# integratedBertha.net
KiCad netlist of a schematic drawn in EAGLE
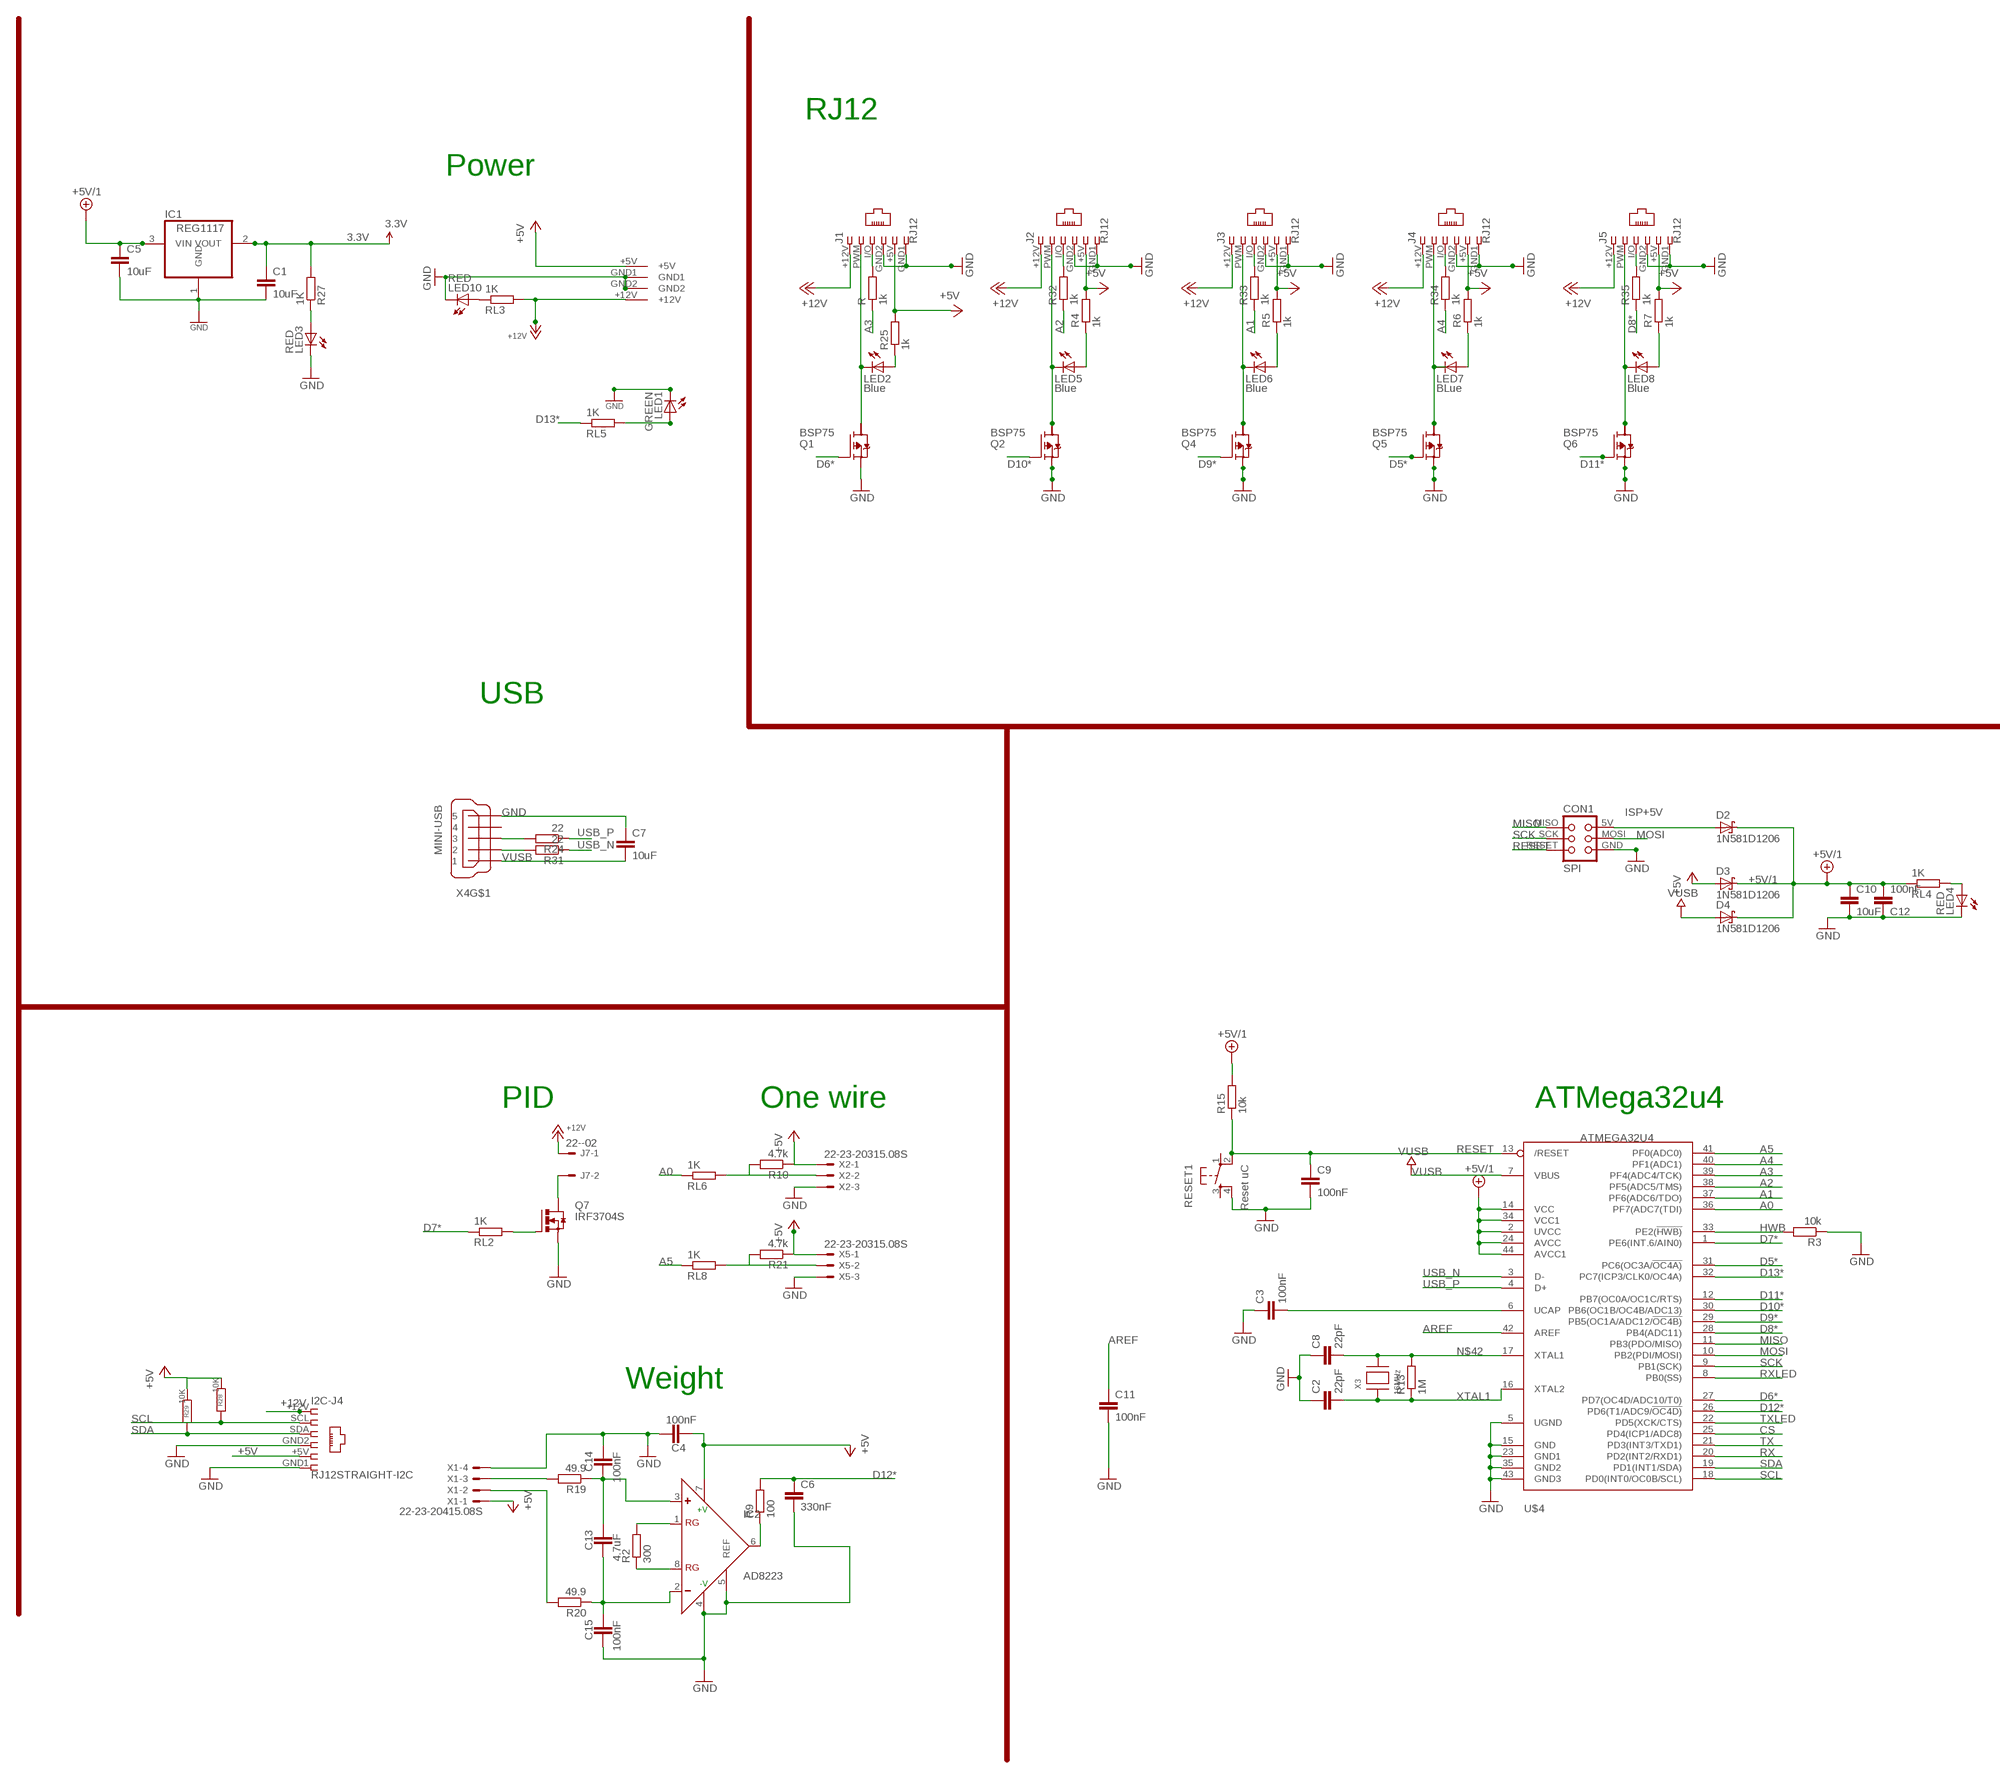
[diagram p0: schematic, sheet 1, part 1 of 2]
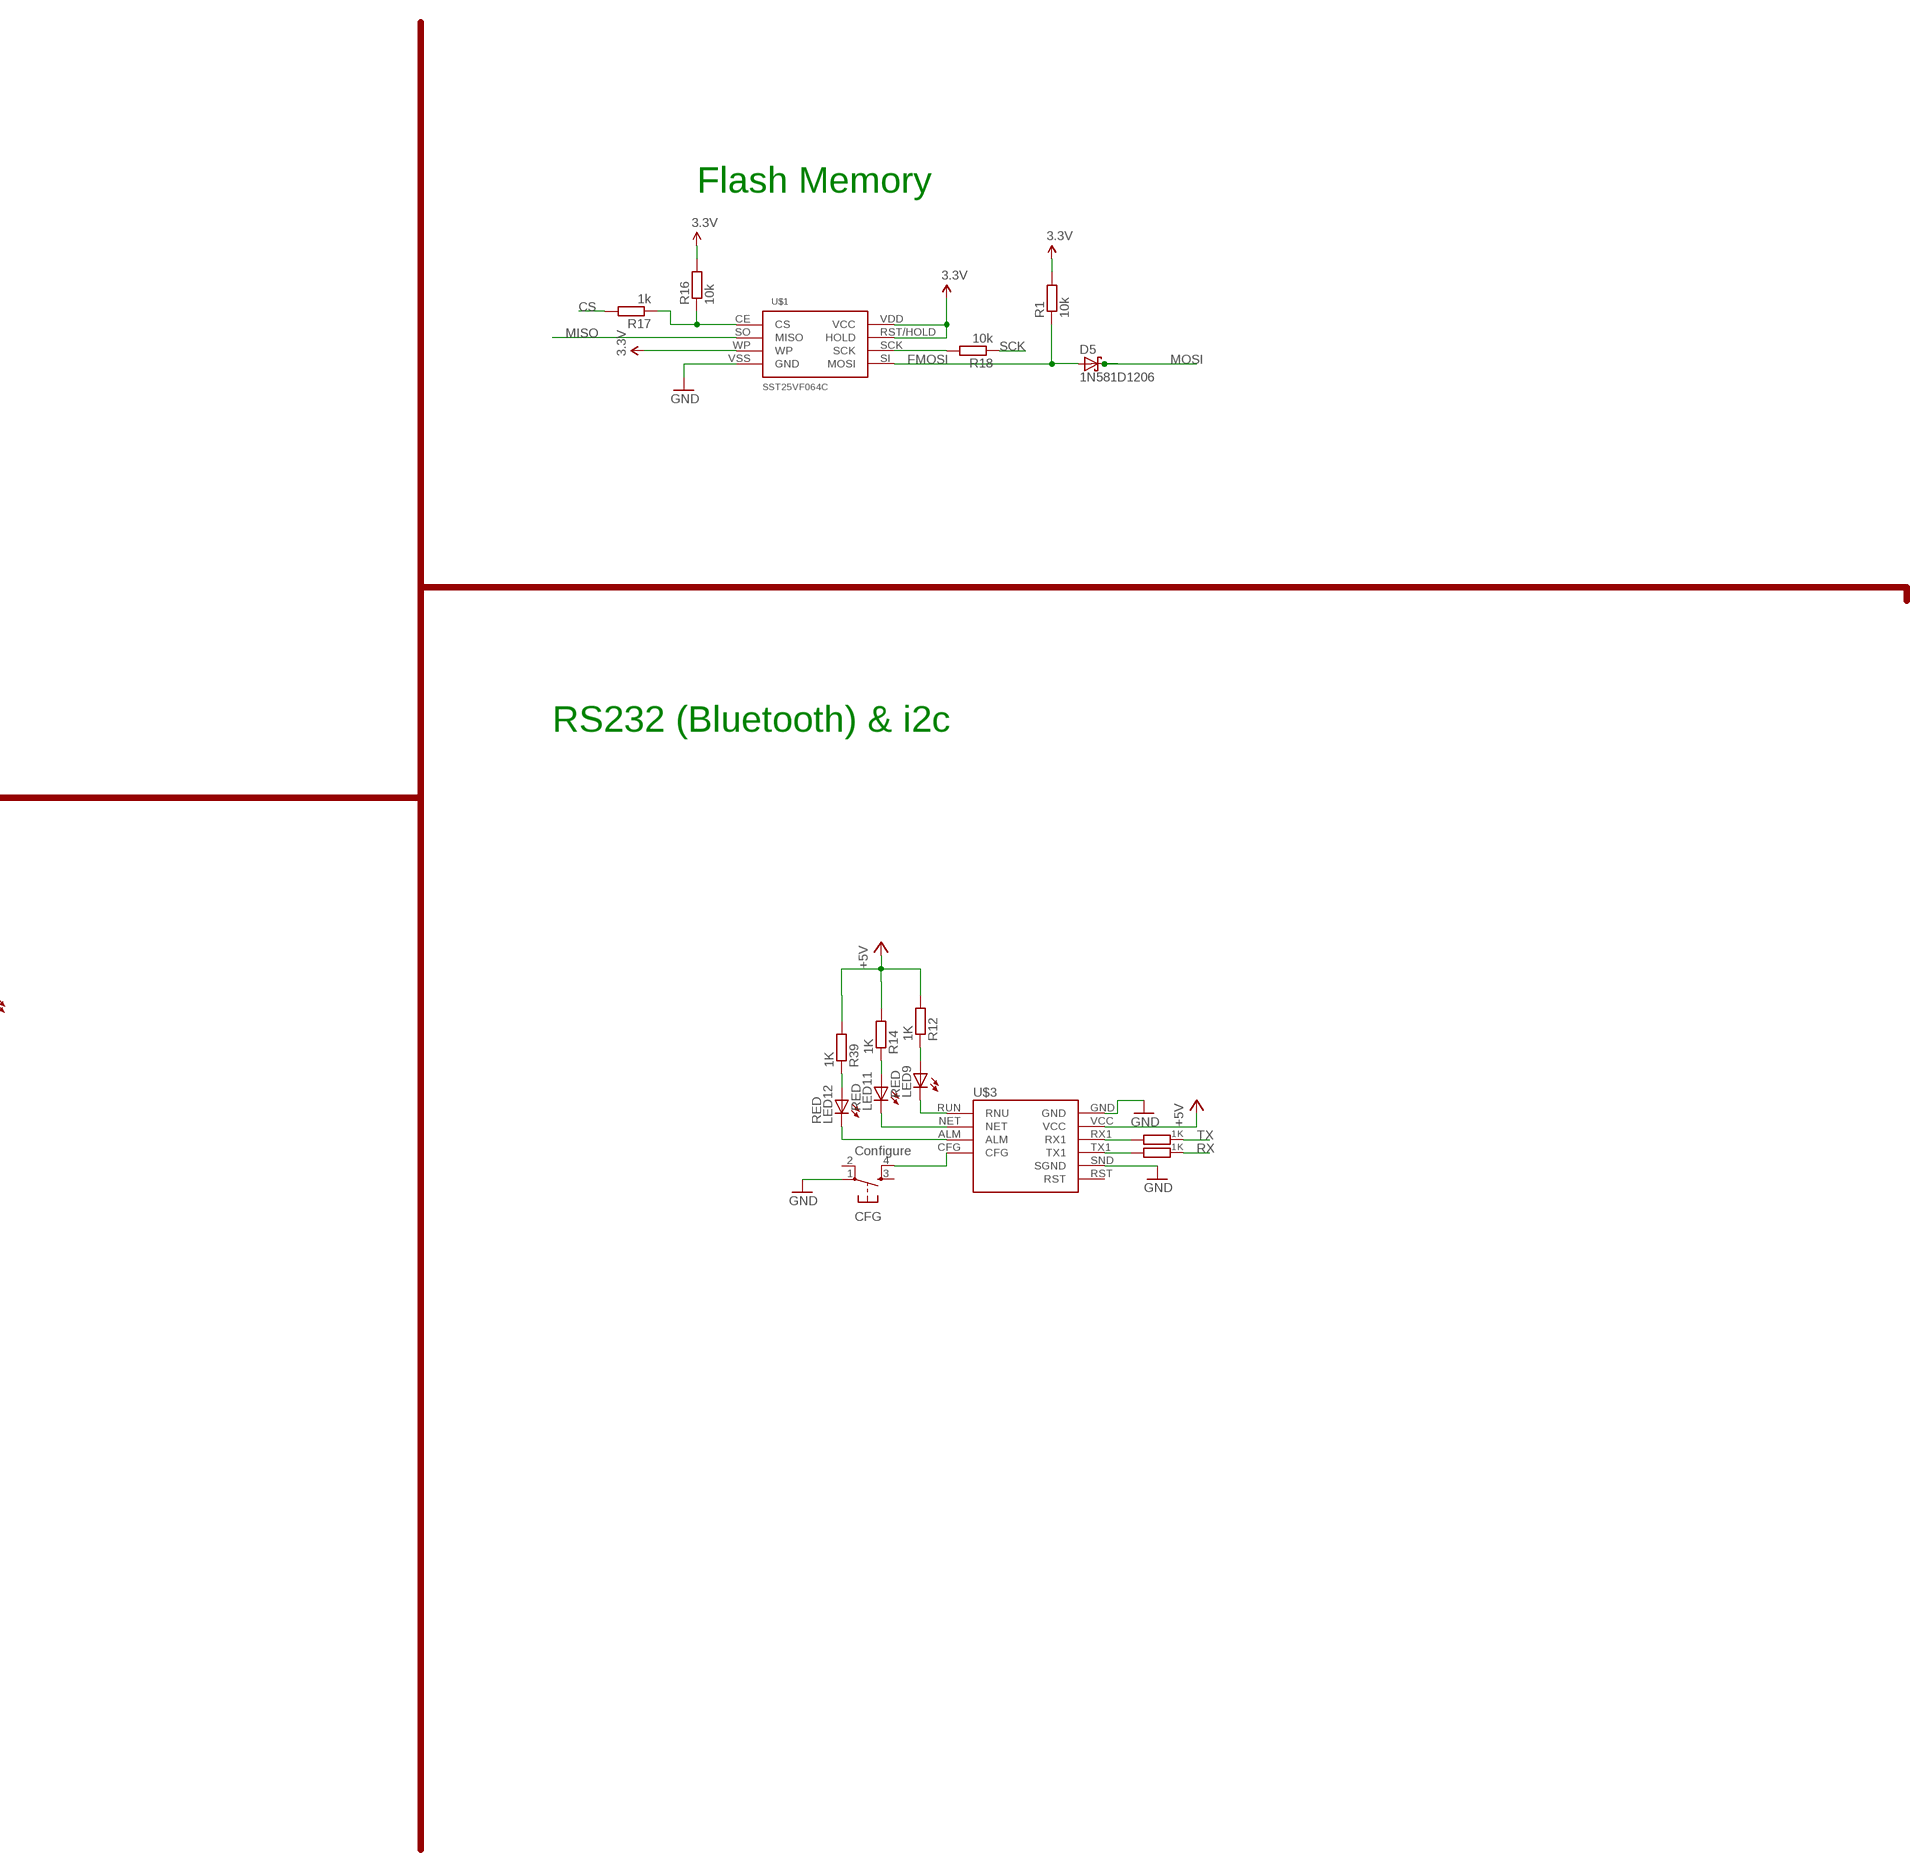
[diagram p1: schematic, sheet 1, part 2 of 2]

(export (version "E")
  (design (tool "Eeschema 10.0.6"))
  (components
    (comp (ref "C1")
      (value "10uF")
      (footprint "eagle-import:C1206")
      (libsource (lib "eagle-import") (part "C-EUC1206"))
    )
    (comp (ref "C2")
      (value "22pF")
      (footprint "eagle-import:C1206")
      (libsource (lib "eagle-import") (part "C-EUC1206"))
    )
    (comp (ref "C3")
      (value "100nF")
      (footprint "eagle-import:C1206")
      (libsource (lib "eagle-import") (part "C-EUC1206"))
    )
    (comp (ref "C4")
      (value "100nF")
      (footprint "eagle-import:C1206")
      (libsource (lib "eagle-import") (part "C-EUC1206"))
    )
    (comp (ref "C5")
      (value "10uF")
      (footprint "eagle-import:C1206")
      (libsource (lib "eagle-import") (part "C-EUC1206"))
    )
    (comp (ref "C6")
      (value "330nF")
      (footprint "eagle-import:C1206")
      (libsource (lib "eagle-import") (part "C-EUC1206"))
    )
    (comp (ref "C7")
      (value "10uF")
      (footprint "eagle-import:C1206")
      (libsource (lib "eagle-import") (part "C-EUC1206"))
    )
    (comp (ref "C8")
      (value "22pF")
      (footprint "eagle-import:C1206")
      (libsource (lib "eagle-import") (part "C-EUC1206"))
    )
    (comp (ref "C9")
      (value "100nF")
      (footprint "eagle-import:C1206")
      (libsource (lib "eagle-import") (part "C-EUC1206"))
    )
    (comp (ref "C10")
      (value "10uF")
      (footprint "eagle-import:C1206")
      (libsource (lib "eagle-import") (part "C-EUC1206"))
    )
    (comp (ref "C11")
      (value "100nF")
      (footprint "eagle-import:C1206")
      (libsource (lib "eagle-import") (part "C-EUC1206"))
    )
    (comp (ref "C12")
      (value "100nF")
      (footprint "eagle-import:C1206")
      (libsource (lib "eagle-import") (part "C-EUC1206"))
    )
    (comp (ref "C13")
      (value "4.7uF")
      (footprint "eagle-import:C1206")
      (libsource (lib "eagle-import") (part "C-EUC1206"))
    )
    (comp (ref "C14")
      (value "100nF")
      (footprint "eagle-import:C1206")
      (libsource (lib "eagle-import") (part "C-EUC1206"))
    )
    (comp (ref "C15")
      (value "100nF")
      (footprint "eagle-import:C1206")
      (libsource (lib "eagle-import") (part "C-EUC1206"))
    )
    (comp (ref "CFG")
      (value "Configure")
      (footprint "eagle-import:TACTILE_SWITCH_SMD")
      (libsource (lib "eagle-import") (part "TAC_SWITCHSMD"))
    )
    (comp (ref "CON1")
      (value "SPI")
      (footprint "eagle-import:TC2030-MCP-NL")
      (libsource (lib "eagle-import") (part "TINYISPT"))
    )
    (comp (ref "D2")
      (value "1N581D1206")
      (footprint "eagle-import:LED-1206")
      (libsource (lib "eagle-import") (part "1N581D1206"))
    )
    (comp (ref "D3")
      (value "1N581D1206")
      (footprint "eagle-import:LED-1206")
      (libsource (lib "eagle-import") (part "1N581D1206"))
    )
    (comp (ref "D4")
      (value "1N581D1206")
      (footprint "eagle-import:LED-1206")
      (libsource (lib "eagle-import") (part "1N581D1206"))
    )
    (comp (ref "D5")
      (value "1N581D1206")
      (footprint "eagle-import:LED-1206")
      (libsource (lib "eagle-import") (part "1N581D1206"))
    )
    (comp (ref "I2C-J4")
      (value "RJ12STRAIGHT-I2C")
      (footprint "eagle-import:RJ12-STRAIGHT-I2C")
      (libsource (lib "eagle-import") (part "RJ12STRAIGHT-I2C"))
    )
    (comp (ref "IC1")
      (value "REG1117")
      (footprint "eagle-import:SOT223")
      (libsource (lib "eagle-import") (part "REG1117"))
    )
    (comp (ref "IC2")
      (value "AD8223")
      (footprint "eagle-import:SO8")
      (fields (field (name "MPN") "AD620AR"))
      (libsource (lib "eagle-import") (part "AD620R"))
    )
    (comp (ref "J1")
      (value "RJ12")
      (footprint "eagle-import:RJ12-STRAIGHT")
      (libsource (lib "eagle-import") (part "RJ12STRAIGHT"))
    )
    (comp (ref "J2")
      (value "RJ12")
      (footprint "eagle-import:RJ12-STRAIGHT")
      (libsource (lib "eagle-import") (part "RJ12STRAIGHT"))
    )
    (comp (ref "J3")
      (value "RJ12")
      (footprint "eagle-import:RJ12-STRAIGHT")
      (libsource (lib "eagle-import") (part "RJ12STRAIGHT"))
    )
    (comp (ref "J4")
      (value "RJ12")
      (footprint "eagle-import:RJ12-STRAIGHT")
      (libsource (lib "eagle-import") (part "RJ12STRAIGHT"))
    )
    (comp (ref "J5")
      (value "RJ12")
      (footprint "eagle-import:RJ12-STRAIGHT")
      (libsource (lib "eagle-import") (part "RJ12STRAIGHT"))
    )
    (comp (ref "J7")
      (value "22--02")
      (footprint "eagle-import:2-PIN-5.08S")
      (libsource (lib "eagle-import") (part "22-?-02"))
    )
    (comp (ref "LED1")
      (value "GREEN")
      (footprint "eagle-import:CHIPLED_1206")
      (libsource (lib "eagle-import") (part "LEDCHIPLED_1206"))
    )
    (comp (ref "LED2")
      (value "Blue")
      (footprint "eagle-import:CHIPLED_1206")
      (libsource (lib "eagle-import") (part "LEDCHIPLED_1206"))
    )
    (comp (ref "LED3")
      (value "RED")
      (footprint "eagle-import:CHIPLED_1206")
      (libsource (lib "eagle-import") (part "LEDCHIPLED_1206"))
    )
    (comp (ref "LED4")
      (value "RED")
      (footprint "eagle-import:CHIPLED_1206")
      (libsource (lib "eagle-import") (part "LEDCHIPLED_1206"))
    )
    (comp (ref "LED5")
      (value "Blue")
      (footprint "eagle-import:CHIPLED_1206")
      (libsource (lib "eagle-import") (part "LEDCHIPLED_1206"))
    )
    (comp (ref "LED6")
      (value "Blue")
      (footprint "eagle-import:CHIPLED_1206")
      (libsource (lib "eagle-import") (part "LEDCHIPLED_1206"))
    )
    (comp (ref "LED7")
      (value "BLue")
      (footprint "eagle-import:CHIPLED_1206")
      (libsource (lib "eagle-import") (part "LEDCHIPLED_1206"))
    )
    (comp (ref "LED8")
      (value "Blue")
      (footprint "eagle-import:CHIPLED_1206")
      (libsource (lib "eagle-import") (part "LEDCHIPLED_1206"))
    )
    (comp (ref "LED9")
      (value "RED")
      (footprint "eagle-import:CHIPLED_1206")
      (libsource (lib "eagle-import") (part "LEDCHIPLED_1206"))
    )
    (comp (ref "LED10")
      (value "RED")
      (footprint "eagle-import:CHIPLED_1206")
      (libsource (lib "eagle-import") (part "LEDCHIPLED_1206"))
    )
    (comp (ref "LED11")
      (value "RED")
      (footprint "eagle-import:CHIPLED_1206")
      (libsource (lib "eagle-import") (part "LEDCHIPLED_1206"))
    )
    (comp (ref "LED12")
      (value "RED")
      (footprint "eagle-import:CHIPLED_1206")
      (libsource (lib "eagle-import") (part "LEDCHIPLED_1206"))
    )
    (comp (ref "Q1")
      (value "BSP75")
      (footprint "eagle-import:PG-SOT-223")
      (libsource (lib "eagle-import") (part "BSP613P"))
    )
    (comp (ref "Q2")
      (value "BSP75")
      (footprint "eagle-import:PG-SOT-223")
      (libsource (lib "eagle-import") (part "BSP613P"))
    )
    (comp (ref "Q4")
      (value "BSP75")
      (footprint "eagle-import:PG-SOT-223")
      (libsource (lib "eagle-import") (part "BSP613P"))
    )
    (comp (ref "Q5")
      (value "BSP75")
      (footprint "eagle-import:PG-SOT-223")
      (libsource (lib "eagle-import") (part "BSP613P"))
    )
    (comp (ref "Q6")
      (value "BSP75")
      (footprint "eagle-import:PG-SOT-223")
      (libsource (lib "eagle-import") (part "BSP613P"))
    )
    (comp (ref "Q7")
      (value "IRF3704S")
      (footprint "eagle-import:D2PACK")
      (libsource (lib "eagle-import") (part "IRF3704S"))
    )
    (comp (ref "R")
      (value "1k")
      (footprint "eagle-import:R0805")
      (libsource (lib "eagle-import") (part "R-EU_R0805"))
    )
    (comp (ref "R1")
      (value "10k")
      (footprint "eagle-import:R0805")
      (libsource (lib "eagle-import") (part "R-EU_R0805"))
    )
    (comp (ref "R2")
      (value "300")
      (footprint "eagle-import:R1206")
      (libsource (lib "eagle-import") (part "resistor_R-EU_R1206"))
    )
    (comp (ref "R3")
      (value "10k")
      (footprint "eagle-import:M0805")
      (libsource (lib "eagle-import") (part "resistor_R-EU_M0805"))
    )
    (comp (ref "R4")
      (value "1k")
      (footprint "eagle-import:R0805")
      (libsource (lib "eagle-import") (part "R-EU_R0805"))
    )
    (comp (ref "R5")
      (value "1k")
      (footprint "eagle-import:R0805")
      (libsource (lib "eagle-import") (part "R-EU_R0805"))
    )
    (comp (ref "R6")
      (value "1k")
      (footprint "eagle-import:R0805")
      (libsource (lib "eagle-import") (part "R-EU_R0805"))
    )
    (comp (ref "R7")
      (value "1k")
      (footprint "eagle-import:R0805")
      (libsource (lib "eagle-import") (part "R-EU_R0805"))
    )
    (comp (ref "R8")
      (value "1K")
      (footprint "eagle-import:R0805")
      (libsource (lib "eagle-import") (part "R-EU_R0805"))
    )
    (comp (ref "R9")
      (value "100")
      (footprint "eagle-import:R1206")
      (libsource (lib "eagle-import") (part "resistor_R-EU_R1206"))
    )
    (comp (ref "R10")
      (value "4.7k")
      (footprint "eagle-import:R1206")
      (libsource (lib "eagle-import") (part "resistor_R-EU_R1206"))
    )
    (comp (ref "R11")
      (value "1K")
      (footprint "eagle-import:R0805")
      (libsource (lib "eagle-import") (part "R-EU_R0805"))
    )
    (comp (ref "R12")
      (value "1K")
      (footprint "eagle-import:R0805")
      (libsource (lib "eagle-import") (part "R-EU_R0805"))
    )
    (comp (ref "R13")
      (value "1M")
      (footprint "eagle-import:R1206")
      (libsource (lib "eagle-import") (part "R-EU_R1206"))
    )
    (comp (ref "R14")
      (value "1K")
      (footprint "eagle-import:R0805")
      (libsource (lib "eagle-import") (part "R-EU_R0805"))
    )
    (comp (ref "R15")
      (value "10k")
      (footprint "eagle-import:M0805")
      (libsource (lib "eagle-import") (part "resistor_R-EU_M0805"))
    )
    (comp (ref "R16")
      (value "10k")
      (footprint "eagle-import:R0805")
      (libsource (lib "eagle-import") (part "R-EU_R0805"))
    )
    (comp (ref "R17")
      (value "1k")
      (footprint "eagle-import:R0805")
      (libsource (lib "eagle-import") (part "R-EU_R0805"))
    )
    (comp (ref "R18")
      (value "10k")
      (footprint "eagle-import:R0805")
      (libsource (lib "eagle-import") (part "R-EU_R0805"))
    )
    (comp (ref "R19")
      (value "49.9")
      (footprint "eagle-import:R1206")
      (libsource (lib "eagle-import") (part "resistor_R-EU_R1206"))
    )
    (comp (ref "R20")
      (value "49.9")
      (footprint "eagle-import:R1206")
      (libsource (lib "eagle-import") (part "resistor_R-EU_R1206"))
    )
    (comp (ref "R21")
      (value "4.7k")
      (footprint "eagle-import:R1206")
      (libsource (lib "eagle-import") (part "resistor_R-EU_R1206"))
    )
    (comp (ref "R24")
      (value "22")
      (footprint "eagle-import:M1206")
      (libsource (lib "eagle-import") (part "resistor_R-EU_M1206"))
    )
    (comp (ref "R25")
      (value "1k")
      (footprint "eagle-import:R0805")
      (libsource (lib "eagle-import") (part "R-EU_R0805"))
    )
    (comp (ref "R27")
      (value "1K")
      (footprint "eagle-import:R0805")
      (libsource (lib "eagle-import") (part "R-EU_R0805"))
    )
    (comp (ref "R28")
      (value "10K")
      (footprint "eagle-import:M0805")
      (libsource (lib "eagle-import") (part "resistor_R-EU_M0805"))
    )
    (comp (ref "R29")
      (value "10K")
      (footprint "eagle-import:M0805")
      (libsource (lib "eagle-import") (part "resistor_R-EU_M0805"))
    )
    (comp (ref "R31")
      (value "22")
      (footprint "eagle-import:M1206")
      (libsource (lib "eagle-import") (part "resistor_R-EU_M1206"))
    )
    (comp (ref "R32")
      (value "1k")
      (footprint "eagle-import:R0805")
      (libsource (lib "eagle-import") (part "R-EU_R0805"))
    )
    (comp (ref "R33")
      (value "1k")
      (footprint "eagle-import:R0805")
      (libsource (lib "eagle-import") (part "R-EU_R0805"))
    )
    (comp (ref "R34")
      (value "1k")
      (footprint "eagle-import:R0805")
      (libsource (lib "eagle-import") (part "R-EU_R0805"))
    )
    (comp (ref "R35")
      (value "1k")
      (footprint "eagle-import:R0805")
      (libsource (lib "eagle-import") (part "R-EU_R0805"))
    )
    (comp (ref "R39")
      (value "1K")
      (footprint "eagle-import:R0805")
      (libsource (lib "eagle-import") (part "R-EU_R0805"))
    )
    (comp (ref "RESET1")
      (value "Reset uC")
      (footprint "eagle-import:TACTILE_SWITCH_SMD")
      (libsource (lib "eagle-import") (part "TAC_SWITCHSMD"))
    )
    (comp (ref "RL2")
      (value "1K")
      (footprint "eagle-import:R0805")
      (libsource (lib "eagle-import") (part "R-EU_R0805"))
    )
    (comp (ref "RL3")
      (value "1K")
      (footprint "eagle-import:R0805")
      (libsource (lib "eagle-import") (part "R-EU_R0805"))
    )
    (comp (ref "RL4")
      (value "1K")
      (footprint "eagle-import:R0805")
      (libsource (lib "eagle-import") (part "resistor_R-EU_R0805"))
    )
    (comp (ref "RL5")
      (value "1K")
      (footprint "eagle-import:R0805")
      (libsource (lib "eagle-import") (part "R-EU_R0805"))
    )
    (comp (ref "RL6")
      (value "1K")
      (footprint "eagle-import:R0805")
      (libsource (lib "eagle-import") (part "R-EU_R0805"))
    )
    (comp (ref "RL8")
      (value "1K")
      (footprint "eagle-import:R0805")
      (libsource (lib "eagle-import") (part "R-EU_R0805"))
    )
    (comp (ref "U$1")
      (value "SST25VF064C")
      (footprint "eagle-import:SOIC_8-LEAD")
      (libsource (lib "eagle-import") (part "SST25VF064C"))
    )
    (comp (ref "U$3")
      (value "SZ05-ZIGBEETHROUGHHOLE")
      (footprint "eagle-import:SZ05-ZIGBEE4")
      (libsource (lib "eagle-import") (part "SZ05-ZIGBEETHROUGHHOLE"))
    )
    (comp (ref "U$4")
      (value "ATMEGA32U4")
      (footprint "eagle-import:TQFP44")
      (libsource (lib "eagle-import") (part "ATMEGA32U4-AU"))
    )
    (comp (ref "U$6")
      (value "KPJX-4S-S")
      (footprint "eagle-import:KPJX-4S-S")
      (libsource (lib "eagle-import") (part "KPJX-4S-S"))
    )
    (comp (ref "X1")
      (value "22-23-20415.08S")
      (footprint "eagle-import:4-PIN-5.08S")
      (libsource (lib "eagle-import") (part "22-23-20415.08S"))
    )
    (comp (ref "X2")
      (value "22-23-20315.08S")
      (footprint "eagle-import:3-PIN-5.08S")
      (libsource (lib "eagle-import") (part "22-23-20315.08S"))
    )
    (comp (ref "X3")
      (value "16MHz")
      (footprint "eagle-import:NX6035")
      (libsource (lib "eagle-import") (part "XTALNX6035"))
    )
    (comp (ref "X4")
      (value "MINI-USB")
      (footprint "eagle-import:32005-201")
      (libsource (lib "eagle-import") (part "MINI-USB-SCHIELD-32005-201"))
    )
    (comp (ref "X5")
      (value "22-23-20315.08S")
      (footprint "eagle-import:3-PIN-5.08S")
      (libsource (lib "eagle-import") (part "22-23-20315.08S"))
    )
  )
  (nets
    (net (code "1") (name "+5V") (class "Default")
      (node (ref "C4") (pin "2") (pinfunction "2_2") (pintype "passive"))
      (node (ref "D3") (pin "A") (pinfunction "A_A") (pintype "passive"))
      (node (ref "I2C-J4") (pin "+5V") (pinfunction "5_+5V") (pintype "bidirectional"))
      (node (ref "IC2") (pin "7") (pinfunction "+V_7") (pintype "power_in"))
      (node (ref "J1") (pin "+5V") (pinfunction "5_+5V") (pintype "bidirectional"))
      (node (ref "J2") (pin "+5V") (pinfunction "5_+5V") (pintype "bidirectional"))
      (node (ref "J3") (pin "+5V") (pinfunction "5_+5V") (pintype "bidirectional"))
      (node (ref "J4") (pin "+5V") (pinfunction "5_+5V") (pintype "bidirectional"))
      (node (ref "J5") (pin "+5V") (pinfunction "5_+5V") (pintype "bidirectional"))
      (node (ref "R10") (pin "1") (pinfunction "1_1") (pintype "passive"))
      (node (ref "R12") (pin "2") (pinfunction "2_2") (pintype "passive"))
      (node (ref "R14") (pin "2") (pinfunction "2_2") (pintype "passive"))
      (node (ref "R21") (pin "1") (pinfunction "1_1") (pintype "passive"))
      (node (ref "R25") (pin "2") (pinfunction "2_2") (pintype "passive"))
      (node (ref "R28") (pin "1") (pinfunction "1_1") (pintype "passive"))
      (node (ref "R29") (pin "1") (pinfunction "1_1") (pintype "passive"))
      (node (ref "R39") (pin "2") (pinfunction "2_2") (pintype "passive"))
      (node (ref "R4") (pin "2") (pinfunction "2_2") (pintype "passive"))
      (node (ref "R5") (pin "2") (pinfunction "2_2") (pintype "passive"))
      (node (ref "R6") (pin "2") (pinfunction "2_2") (pintype "passive"))
      (node (ref "R7") (pin "2") (pinfunction "2_2") (pintype "passive"))
      (node (ref "U$3") (pin "VCC") (pinfunction "VCC_VCC") (pintype "bidirectional"))
      (node (ref "U$6") (pin "+5V") (pinfunction "+5V_+5V") (pintype "power_in"))
      (node (ref "X1") (pin "1") (pinfunction "S_1") (pintype "passive"))
      (node (ref "X2") (pin "1") (pinfunction "S_1") (pintype "passive"))
      (node (ref "X5") (pin "1") (pinfunction "S_1") (pintype "passive"))
    )
    (net (code "2") (name "+5V{slash}1") (class "Default")
      (node (ref "C10") (pin "1") (pinfunction "1_1") (pintype "passive"))
      (node (ref "C12") (pin "2") (pinfunction "2_2") (pintype "passive"))
      (node (ref "C5") (pin "1") (pinfunction "1_1") (pintype "passive"))
      (node (ref "D2") (pin "C") (pinfunction "C_C") (pintype "passive"))
      (node (ref "D3") (pin "C") (pinfunction "C_C") (pintype "passive"))
      (node (ref "D4") (pin "C") (pinfunction "C_C") (pintype "passive"))
      (node (ref "IC1") (pin "3") (pinfunction "VIN_3") (pintype "input"))
      (node (ref "R15") (pin "2") (pinfunction "2_2") (pintype "passive"))
      (node (ref "RL4") (pin "1") (pinfunction "1_1") (pintype "passive"))
      (node (ref "U$4") (pin "14") (pinfunction "VCC_14") (pintype "bidirectional"))
      (node (ref "U$4") (pin "2") (pinfunction "UVCC_2") (pintype "bidirectional"))
      (node (ref "U$4") (pin "24") (pinfunction "AVCC_24") (pintype "bidirectional"))
      (node (ref "U$4") (pin "34") (pinfunction "VCC1_34") (pintype "bidirectional"))
      (node (ref "U$4") (pin "44") (pinfunction "AVCC1_44") (pintype "bidirectional"))
    )
    (net (code "3") (name "+12V") (class "Default")
      (node (ref "I2C-J4") (pin "+12V") (pinfunction "1_+12V") (pintype "bidirectional"))
      (node (ref "J1") (pin "+12V") (pinfunction "1_+12V") (pintype "bidirectional"))
      (node (ref "J2") (pin "+12V") (pinfunction "1_+12V") (pintype "bidirectional"))
      (node (ref "J3") (pin "+12V") (pinfunction "1_+12V") (pintype "bidirectional"))
      (node (ref "J4") (pin "+12V") (pinfunction "1_+12V") (pintype "bidirectional"))
      (node (ref "J5") (pin "+12V") (pinfunction "1_+12V") (pintype "bidirectional"))
      (node (ref "J7") (pin "1") (pinfunction "S_1") (pintype "passive"))
      (node (ref "RL3") (pin "2") (pinfunction "2_2") (pintype "passive"))
      (node (ref "U$6") (pin "+12V") (pinfunction "+12V_+12V") (pintype "power_in"))
    )
    (net (code "4") (name "/A0") (class "Default")
      (node (ref "RL6") (pin "1") (pinfunction "1_1") (pintype "passive"))
      (node (ref "U$4") (pin "36") (pinfunction "PF7(ADC7(TDI)_36") (pintype "bidirectional"))
    )
    (net (code "5") (name "/A1") (class "Default")
      (node (ref "R33") (pin "1") (pinfunction "1_1") (pintype "passive"))
      (node (ref "U$4") (pin "37") (pinfunction "PF6(ADC6/TDO)_37") (pintype "bidirectional"))
    )
    (net (code "6") (name "/A2") (class "Default")
      (node (ref "R32") (pin "1") (pinfunction "1_1") (pintype "passive"))
      (node (ref "U$4") (pin "38") (pinfunction "PF5(ADC5/TMS)_38") (pintype "bidirectional"))
    )
    (net (code "7") (name "/A3") (class "Default")
      (node (ref "R") (pin "1") (pinfunction "1_1") (pintype "passive"))
      (node (ref "U$4") (pin "39") (pinfunction "PF4(ADC4/TCK)_39") (pintype "bidirectional"))
    )
    (net (code "8") (name "/A4") (class "Default")
      (node (ref "R34") (pin "1") (pinfunction "1_1") (pintype "passive"))
      (node (ref "U$4") (pin "40") (pinfunction "PF1(ADC1)_40") (pintype "bidirectional"))
    )
    (net (code "9") (name "/A5") (class "Default")
      (node (ref "RL8") (pin "1") (pinfunction "1_1") (pintype "passive"))
      (node (ref "U$4") (pin "41") (pinfunction "PF0(ADC0)_41") (pintype "bidirectional"))
    )
    (net (code "10") (name "/AREF") (class "Default")
      (node (ref "C11") (pin "1") (pinfunction "1_1") (pintype "passive"))
      (node (ref "U$4") (pin "42") (pinfunction "AREF_42") (pintype "bidirectional"))
    )
    (net (code "11") (name "/CS") (class "Default")
      (node (ref "R17") (pin "2") (pinfunction "2_2") (pintype "passive"))
      (node (ref "U$4") (pin "25") (pinfunction "PD4(ICP1/ADC8)_25") (pintype "bidirectional"))
    )
    (net (code "12") (name "/D5*") (class "Default")
      (node (ref "Q5") (pin "1") (pinfunction "G_1") (pintype "passive"))
      (node (ref "U$4") (pin "31") (pinfunction "PC6(OC3A/~{OC4A})_31") (pintype "bidirectional"))
    )
    (net (code "13") (name "/D6*") (class "Default")
      (node (ref "Q1") (pin "1") (pinfunction "G_1") (pintype "passive"))
      (node (ref "U$4") (pin "27") (pinfunction "PD7(OC4D/ADC10/T0)_27") (pintype "bidirectional"))
    )
    (net (code "14") (name "/D7*") (class "Default")
      (node (ref "RL2") (pin "1") (pinfunction "1_1") (pintype "passive"))
      (node (ref "U$4") (pin "1") (pinfunction "PE6(INT.6/AIN0)_1") (pintype "bidirectional"))
    )
    (net (code "15") (name "/D8*") (class "Default")
      (node (ref "R35") (pin "1") (pinfunction "1_1") (pintype "passive"))
      (node (ref "U$4") (pin "28") (pinfunction "PB4(ADC11)_28") (pintype "bidirectional"))
    )
    (net (code "16") (name "/D9*") (class "Default")
      (node (ref "Q4") (pin "1") (pinfunction "G_1") (pintype "passive"))
      (node (ref "U$4") (pin "29") (pinfunction "PB5(OC1A/ADC12/~{OC4B})_29") (pintype "bidirectional"))
    )
    (net (code "17") (name "/D10*") (class "Default")
      (node (ref "Q2") (pin "1") (pinfunction "G_1") (pintype "passive"))
      (node (ref "U$4") (pin "30") (pinfunction "PB6(OC1B/OC4B/ADC13)_30") (pintype "bidirectional"))
    )
    (net (code "18") (name "/D11*") (class "Default")
      (node (ref "Q6") (pin "1") (pinfunction "G_1") (pintype "passive"))
      (node (ref "U$4") (pin "12") (pinfunction "PB7(OC0A/OC1C/RTS)_12") (pintype "bidirectional"))
    )
    (net (code "19") (name "/D12*") (class "Default")
      (node (ref "C6") (pin "1") (pinfunction "1_1") (pintype "passive"))
      (node (ref "R9") (pin "2") (pinfunction "2_2") (pintype "passive"))
      (node (ref "U$4") (pin "26") (pinfunction "PD6(T1/ADC9/~{OC4D})_26") (pintype "bidirectional"))
    )
    (net (code "20") (name "/D13*") (class "Default")
      (node (ref "RL5") (pin "1") (pinfunction "1_1") (pintype "passive"))
      (node (ref "U$4") (pin "32") (pinfunction "PC7(ICP3/CLK0/OC4A)_32") (pintype "bidirectional"))
    )
    (net (code "21") (name "/FMOSI") (class "Default")
      (node (ref "D5") (pin "A") (pinfunction "A_A") (pintype "passive"))
      (node (ref "R1") (pin "1") (pinfunction "1_1") (pintype "passive"))
      (node (ref "U$1") (pin "SI") (pinfunction "MOSI_SI") (pintype "bidirectional"))
    )
    (net (code "22") (name "/HWB") (class "Default")
      (node (ref "R3") (pin "2") (pinfunction "2_2") (pintype "passive"))
      (node (ref "U$4") (pin "33") (pinfunction "PE2(~{HWB})_33") (pintype "bidirectional"))
    )
    (net (code "23") (name "/ISP+5V") (class "Default")
      (node (ref "CON1") (pin "5V") (pinfunction "VCC_5V") (pintype "passive"))
      (node (ref "D2") (pin "A") (pinfunction "A_A") (pintype "passive"))
    )
    (net (code "24") (name "/MISO") (class "Default")
      (node (ref "CON1") (pin "MISO") (pinfunction "MISO_MISO") (pintype "passive"))
      (node (ref "U$1") (pin "SO") (pinfunction "MISO_SO") (pintype "bidirectional"))
      (node (ref "U$4") (pin "11") (pinfunction "PB3(PDO/MISO)_11") (pintype "bidirectional"))
    )
    (net (code "25") (name "/MOSI") (class "Default")
      (node (ref "CON1") (pin "MOSI") (pinfunction "MOSI_MOSI") (pintype "passive"))
      (node (ref "D5") (pin "C") (pinfunction "C_C") (pintype "passive"))
      (node (ref "U$4") (pin "10") (pinfunction "PB2(PDI/MOSI)_10") (pintype "bidirectional"))
    )
    (net (code "26") (name "/N$42") (class "Default")
      (node (ref "C8") (pin "2") (pinfunction "2_2") (pintype "passive"))
      (node (ref "R13") (pin "2") (pinfunction "2_2") (pintype "passive"))
      (node (ref "U$4") (pin "17") (pinfunction "XTAL1_17") (pintype "bidirectional"))
      (node (ref "X3") (pin "P$2") (pinfunction "P$2_P$2") (pintype "bidirectional"))
    )
    (net (code "27") (name "/RESET") (class "Default")
      (node (ref "C9") (pin "1") (pinfunction "1_1") (pintype "passive"))
      (node (ref "CON1") (pin "RESET") (pinfunction "RESET_RESET") (pintype "passive"))
      (node (ref "R15") (pin "1") (pinfunction "1_1") (pintype "passive"))
      (node (ref "RESET1") (pin "2") (pinfunction "2_2") (pintype "passive"))
      (node (ref "U$4") (pin "13") (pinfunction "/RESET_13") (pintype "bidirectional"))
    )
    (net (code "28") (name "/RX") (class "Default")
      (node (ref "R8") (pin "1") (pinfunction "1_1") (pintype "passive"))
      (node (ref "U$4") (pin "20") (pinfunction "PD2(INT2/RXD1)_20") (pintype "bidirectional"))
    )
    (net (code "29") (name "/RXLED") (class "Default")
      (node (ref "U$4") (pin "8") (pinfunction "PB0(SS)_8") (pintype "bidirectional"))
    )
    (net (code "30") (name "/SCK") (class "Default")
      (node (ref "CON1") (pin "SCK") (pinfunction "SCK_SCK") (pintype "passive"))
      (node (ref "R18") (pin "1") (pinfunction "1_1") (pintype "passive"))
      (node (ref "U$4") (pin "9") (pinfunction "PB1(SCK)_9") (pintype "bidirectional"))
    )
    (net (code "31") (name "/SCL") (class "Default")
      (node (ref "I2C-J4") (pin "SCL") (pinfunction "2_SCL") (pintype "bidirectional"))
      (node (ref "R28") (pin "2") (pinfunction "2_2") (pintype "passive"))
      (node (ref "U$4") (pin "18") (pinfunction "PD0(INT0/OC0B/SCL)_18") (pintype "bidirectional"))
    )
    (net (code "32") (name "/SDA") (class "Default")
      (node (ref "I2C-J4") (pin "SDA") (pinfunction "3_SDA") (pintype "bidirectional"))
      (node (ref "R29") (pin "2") (pinfunction "2_2") (pintype "passive"))
      (node (ref "U$4") (pin "19") (pinfunction "PD1(INT1/SDA)_19") (pintype "bidirectional"))
    )
    (net (code "33") (name "/TX") (class "Default")
      (node (ref "R11") (pin "1") (pinfunction "1_1") (pintype "passive"))
      (node (ref "U$4") (pin "21") (pinfunction "PD3(INT3/TXD1)_21") (pintype "bidirectional"))
    )
    (net (code "34") (name "/TXLED") (class "Default")
      (node (ref "U$4") (pin "22") (pinfunction "PD5(XCK/CTS)_22") (pintype "bidirectional"))
    )
    (net (code "35") (name "/USB_N") (class "Default")
      (node (ref "R31") (pin "1") (pinfunction "1_1") (pintype "passive"))
      (node (ref "U$4") (pin "3") (pinfunction "D-_3") (pintype "bidirectional"))
    )
    (net (code "36") (name "/USB_P") (class "Default")
      (node (ref "R24") (pin "1") (pinfunction "1_1") (pintype "passive"))
      (node (ref "U$4") (pin "4") (pinfunction "D+_4") (pintype "bidirectional"))
    )
    (net (code "37") (name "/XTAL1") (class "Default")
      (node (ref "C2") (pin "2") (pinfunction "2_2") (pintype "passive"))
      (node (ref "R13") (pin "1") (pinfunction "1_1") (pintype "passive"))
      (node (ref "U$4") (pin "16") (pinfunction "XTAL2_16") (pintype "bidirectional"))
      (node (ref "X3") (pin "P$1") (pinfunction "P$1_P$1") (pintype "bidirectional"))
    )
    (net (code "38") (name "3.3V") (class "Default")
      (node (ref "C1") (pin "1") (pinfunction "1_1") (pintype "passive"))
      (node (ref "IC1") (pin "2") (pinfunction "VOUT_2") (pintype "output"))
      (node (ref "R1") (pin "2") (pinfunction "2_2") (pintype "passive"))
      (node (ref "R16") (pin "2") (pinfunction "2_2") (pintype "passive"))
      (node (ref "R27") (pin "2") (pinfunction "2_2") (pintype "passive"))
      (node (ref "U$1") (pin "RST/HOLD") (pinfunction "HOLD_RST/HOLD") (pintype "bidirectional"))
      (node (ref "U$1") (pin "VDD") (pinfunction "VCC_VDD") (pintype "bidirectional"))
      (node (ref "U$1") (pin "WP") (pinfunction "WP_WP") (pintype "bidirectional"))
    )
    (net (code "39") (name "GND") (class "Default")
      (node (ref "C1") (pin "2") (pinfunction "2_2") (pintype "passive"))
      (node (ref "C10") (pin "2") (pinfunction "2_2") (pintype "passive"))
      (node (ref "C11") (pin "2") (pinfunction "2_2") (pintype "passive"))
      (node (ref "C12") (pin "1") (pinfunction "1_1") (pintype "passive"))
      (node (ref "C14") (pin "1") (pinfunction "1_1") (pintype "passive"))
      (node (ref "C15") (pin "2") (pinfunction "2_2") (pintype "passive"))
      (node (ref "C2") (pin "1") (pinfunction "1_1") (pintype "passive"))
      (node (ref "C3") (pin "1") (pinfunction "1_1") (pintype "passive"))
      (node (ref "C4") (pin "1") (pinfunction "1_1") (pintype "passive"))
      (node (ref "C5") (pin "2") (pinfunction "2_2") (pintype "passive"))
      (node (ref "C6") (pin "2") (pinfunction "2_2") (pintype "passive"))
      (node (ref "C7") (pin "1") (pinfunction "1_1") (pintype "passive"))
      (node (ref "C8") (pin "1") (pinfunction "1_1") (pintype "passive"))
      (node (ref "C9") (pin "2") (pinfunction "2_2") (pintype "passive"))
      (node (ref "CFG") (pin "1") (pinfunction "1_1") (pintype "passive"))
      (node (ref "CON1") (pin "GND") (pinfunction "GND_GND") (pintype "passive"))
      (node (ref "I2C-J4") (pin "GND1") (pinfunction "6_GND1") (pintype "bidirectional"))
      (node (ref "I2C-J4") (pin "GND2") (pinfunction "4_GND2") (pintype "bidirectional"))
      (node (ref "IC1") (pin "1") (pinfunction "GND_1") (pintype "power_in"))
      (node (ref "IC2") (pin "4") (pinfunction "-V_4") (pintype "power_in"))
      (node (ref "IC2") (pin "5") (pinfunction "REF_5") (pintype "passive"))
      (node (ref "J1") (pin "GND1") (pinfunction "6_GND1") (pintype "bidirectional"))
      (node (ref "J1") (pin "GND2") (pinfunction "4_GND2") (pintype "bidirectional"))
      (node (ref "J2") (pin "GND1") (pinfunction "6_GND1") (pintype "bidirectional"))
      (node (ref "J2") (pin "GND2") (pinfunction "4_GND2") (pintype "bidirectional"))
      (node (ref "J3") (pin "GND1") (pinfunction "6_GND1") (pintype "bidirectional"))
      (node (ref "J3") (pin "GND2") (pinfunction "4_GND2") (pintype "bidirectional"))
      (node (ref "J4") (pin "GND1") (pinfunction "6_GND1") (pintype "bidirectional"))
      (node (ref "J4") (pin "GND2") (pinfunction "4_GND2") (pintype "bidirectional"))
      (node (ref "J5") (pin "GND1") (pinfunction "6_GND1") (pintype "bidirectional"))
      (node (ref "J5") (pin "GND2") (pinfunction "4_GND2") (pintype "bidirectional"))
      (node (ref "LED1") (pin "C") (pinfunction "C_C") (pintype "passive"))
      (node (ref "LED10") (pin "C") (pinfunction "C_C") (pintype "passive"))
      (node (ref "LED3") (pin "C") (pinfunction "C_C") (pintype "passive"))
      (node (ref "LED4") (pin "C") (pinfunction "C_C") (pintype "passive"))
      (node (ref "Q1") (pin "3") (pinfunction "S_3") (pintype "passive"))
      (node (ref "Q2") (pin "3") (pinfunction "S_3") (pintype "passive"))
      (node (ref "Q4") (pin "3") (pinfunction "S_3") (pintype "passive"))
      (node (ref "Q5") (pin "3") (pinfunction "S_3") (pintype "passive"))
      (node (ref "Q6") (pin "3") (pinfunction "S_3") (pintype "passive"))
      (node (ref "Q7") (pin "3") (pinfunction "S_3") (pintype "passive"))
      (node (ref "R3") (pin "1") (pinfunction "1_1") (pintype "passive"))
      (node (ref "RESET1") (pin "4") (pinfunction "4_4") (pintype "passive"))
      (node (ref "U$1") (pin "VSS") (pinfunction "GND_VSS") (pintype "bidirectional"))
      (node (ref "U$3") (pin "GND") (pinfunction "GND_GND") (pintype "bidirectional"))
      (node (ref "U$3") (pin "SND") (pinfunction "SGND_SND") (pintype "bidirectional"))
      (node (ref "U$4") (pin "15") (pinfunction "GND_15") (pintype "bidirectional"))
      (node (ref "U$4") (pin "23") (pinfunction "GND1_23") (pintype "bidirectional"))
      (node (ref "U$4") (pin "35") (pinfunction "GND2_35") (pintype "bidirectional"))
      (node (ref "U$4") (pin "43") (pinfunction "GND3_43") (pintype "bidirectional"))
      (node (ref "U$4") (pin "5") (pinfunction "UGND_5") (pintype "bidirectional"))
      (node (ref "U$6") (pin "GND1") (pinfunction "GND1_GND1") (pintype "input"))
      (node (ref "U$6") (pin "GND2") (pinfunction "GND2_GND2") (pintype "input"))
      (node (ref "X1") (pin "4") (pinfunction "S_4") (pintype "passive"))
      (node (ref "X2") (pin "3") (pinfunction "S_3") (pintype "passive"))
      (node (ref "X4") (pin "5") (pinfunction "5_5") (pintype "passive"))
      (node (ref "X5") (pin "3") (pinfunction "S_3") (pintype "passive"))
    )
    (net (code "40") (name "Net-(CFG-Pad4)") (class "Default")
      (node (ref "CFG") (pin "4") (pinfunction "4_4") (pintype "passive"))
      (node (ref "U$3") (pin "CFG") (pinfunction "CFG_CFG") (pintype "bidirectional"))
    )
    (net (code "41") (name "Net-(IC2-+)") (class "Default")
      (node (ref "C13") (pin "1") (pinfunction "1_1") (pintype "passive"))
      (node (ref "C14") (pin "2") (pinfunction "2_2") (pintype "passive"))
      (node (ref "IC2") (pin "3") (pinfunction "+_3") (pintype "input"))
      (node (ref "R19") (pin "1") (pinfunction "1_1") (pintype "passive"))
    )
    (net (code "42") (name "Net-(IC2--)") (class "Default")
      (node (ref "C13") (pin "2") (pinfunction "2_2") (pintype "passive"))
      (node (ref "C15") (pin "1") (pinfunction "1_1") (pintype "passive"))
      (node (ref "IC2") (pin "2") (pinfunction "-_2") (pintype "input"))
      (node (ref "R20") (pin "1") (pinfunction "1_1") (pintype "passive"))
    )
    (net (code "43") (name "Net-(IC2-OUT)") (class "Default")
      (node (ref "IC2") (pin "6") (pinfunction "OUT_6") (pintype "output"))
      (node (ref "R9") (pin "1") (pinfunction "1_1") (pintype "passive"))
    )
    (net (code "44") (name "Net-(IC2-RG-Pad1)") (class "Default")
      (node (ref "IC2") (pin "1") (pinfunction "RG_1") (pintype "passive"))
      (node (ref "R2") (pin "2") (pinfunction "2_2") (pintype "passive"))
    )
    (net (code "45") (name "Net-(IC2-RG-Pad8)") (class "Default")
      (node (ref "IC2") (pin "8") (pinfunction "RG_8") (pintype "passive"))
      (node (ref "R2") (pin "1") (pinfunction "1_1") (pintype "passive"))
    )
    (net (code "46") (name "Net-(J1-2)") (class "Default")
      (node (ref "J1") (pin "PWM") (pinfunction "2_PWM") (pintype "bidirectional"))
      (node (ref "LED2") (pin "C") (pinfunction "C_C") (pintype "passive"))
      (node (ref "Q1") (pin "2") (pinfunction "D_2") (pintype "passive"))
    )
    (net (code "47") (name "Net-(J1-3)") (class "Default")
      (node (ref "J1") (pin "I/O") (pinfunction "3_I/O") (pintype "bidirectional"))
      (node (ref "R") (pin "2") (pinfunction "2_2") (pintype "passive"))
    )
    (net (code "48") (name "Net-(J2-2)") (class "Default")
      (node (ref "J2") (pin "PWM") (pinfunction "2_PWM") (pintype "bidirectional"))
      (node (ref "LED5") (pin "C") (pinfunction "C_C") (pintype "passive"))
      (node (ref "Q2") (pin "2") (pinfunction "D_2") (pintype "passive"))
    )
    (net (code "49") (name "Net-(J2-3)") (class "Default")
      (node (ref "J2") (pin "I/O") (pinfunction "3_I/O") (pintype "bidirectional"))
      (node (ref "R32") (pin "2") (pinfunction "2_2") (pintype "passive"))
    )
    (net (code "50") (name "Net-(J3-2)") (class "Default")
      (node (ref "J3") (pin "PWM") (pinfunction "2_PWM") (pintype "bidirectional"))
      (node (ref "LED6") (pin "C") (pinfunction "C_C") (pintype "passive"))
      (node (ref "Q4") (pin "2") (pinfunction "D_2") (pintype "passive"))
    )
    (net (code "51") (name "Net-(J3-3)") (class "Default")
      (node (ref "J3") (pin "I/O") (pinfunction "3_I/O") (pintype "bidirectional"))
      (node (ref "R33") (pin "2") (pinfunction "2_2") (pintype "passive"))
    )
    (net (code "52") (name "Net-(J4-2)") (class "Default")
      (node (ref "J4") (pin "PWM") (pinfunction "2_PWM") (pintype "bidirectional"))
      (node (ref "LED7") (pin "C") (pinfunction "C_C") (pintype "passive"))
      (node (ref "Q5") (pin "2") (pinfunction "D_2") (pintype "passive"))
    )
    (net (code "53") (name "Net-(J4-3)") (class "Default")
      (node (ref "J4") (pin "I/O") (pinfunction "3_I/O") (pintype "bidirectional"))
      (node (ref "R34") (pin "2") (pinfunction "2_2") (pintype "passive"))
    )
    (net (code "54") (name "Net-(J5-2)") (class "Default")
      (node (ref "J5") (pin "PWM") (pinfunction "2_PWM") (pintype "bidirectional"))
      (node (ref "LED8") (pin "C") (pinfunction "C_C") (pintype "passive"))
      (node (ref "Q6") (pin "2") (pinfunction "D_2") (pintype "passive"))
    )
    (net (code "55") (name "Net-(J5-3)") (class "Default")
      (node (ref "J5") (pin "I/O") (pinfunction "3_I/O") (pintype "bidirectional"))
      (node (ref "R35") (pin "2") (pinfunction "2_2") (pintype "passive"))
    )
    (net (code "56") (name "Net-(J7B-S)") (class "Default")
      (node (ref "J7") (pin "2") (pinfunction "S_2") (pintype "passive"))
      (node (ref "Q7") (pin "2") (pinfunction "D_2") (pintype "passive"))
    )
    (net (code "57") (name "Net-(LED1-PadA)") (class "Default")
      (node (ref "LED1") (pin "A") (pinfunction "A_A") (pintype "passive"))
      (node (ref "RL5") (pin "2") (pinfunction "2_2") (pintype "passive"))
    )
    (net (code "58") (name "Net-(LED2-PadA)") (class "Default")
      (node (ref "LED2") (pin "A") (pinfunction "A_A") (pintype "passive"))
      (node (ref "R25") (pin "1") (pinfunction "1_1") (pintype "passive"))
    )
    (net (code "59") (name "Net-(LED3-PadA)") (class "Default")
      (node (ref "LED3") (pin "A") (pinfunction "A_A") (pintype "passive"))
      (node (ref "R27") (pin "1") (pinfunction "1_1") (pintype "passive"))
    )
    (net (code "60") (name "Net-(LED4-PadA)") (class "Default")
      (node (ref "LED4") (pin "A") (pinfunction "A_A") (pintype "passive"))
      (node (ref "RL4") (pin "2") (pinfunction "2_2") (pintype "passive"))
    )
    (net (code "61") (name "Net-(LED5-PadA)") (class "Default")
      (node (ref "LED5") (pin "A") (pinfunction "A_A") (pintype "passive"))
      (node (ref "R4") (pin "1") (pinfunction "1_1") (pintype "passive"))
    )
    (net (code "62") (name "Net-(LED6-PadA)") (class "Default")
      (node (ref "LED6") (pin "A") (pinfunction "A_A") (pintype "passive"))
      (node (ref "R5") (pin "1") (pinfunction "1_1") (pintype "passive"))
    )
    (net (code "63") (name "Net-(LED7-PadA)") (class "Default")
      (node (ref "LED7") (pin "A") (pinfunction "A_A") (pintype "passive"))
      (node (ref "R6") (pin "1") (pinfunction "1_1") (pintype "passive"))
    )
    (net (code "64") (name "Net-(LED8-PadA)") (class "Default")
      (node (ref "LED8") (pin "A") (pinfunction "A_A") (pintype "passive"))
      (node (ref "R7") (pin "1") (pinfunction "1_1") (pintype "passive"))
    )
    (net (code "65") (name "Net-(LED9-PadA)") (class "Default")
      (node (ref "LED9") (pin "A") (pinfunction "A_A") (pintype "passive"))
      (node (ref "R12") (pin "1") (pinfunction "1_1") (pintype "passive"))
    )
    (net (code "66") (name "Net-(LED10-PadA)") (class "Default")
      (node (ref "LED10") (pin "A") (pinfunction "A_A") (pintype "passive"))
      (node (ref "RL3") (pin "1") (pinfunction "1_1") (pintype "passive"))
    )
    (net (code "67") (name "Net-(LED11-PadA)") (class "Default")
      (node (ref "LED11") (pin "A") (pinfunction "A_A") (pintype "passive"))
      (node (ref "R14") (pin "1") (pinfunction "1_1") (pintype "passive"))
    )
    (net (code "68") (name "Net-(LED11-PadC)") (class "Default")
      (node (ref "LED11") (pin "C") (pinfunction "C_C") (pintype "passive"))
      (node (ref "U$3") (pin "NET") (pinfunction "NET_NET") (pintype "bidirectional"))
    )
    (net (code "69") (name "Net-(LED12-PadA)") (class "Default")
      (node (ref "LED12") (pin "A") (pinfunction "A_A") (pintype "passive"))
      (node (ref "R39") (pin "1") (pinfunction "1_1") (pintype "passive"))
    )
    (net (code "70") (name "Net-(LED12-PadC)") (class "Default")
      (node (ref "LED12") (pin "C") (pinfunction "C_C") (pintype "passive"))
      (node (ref "U$3") (pin "ALM") (pinfunction "ALM_ALM") (pintype "bidirectional"))
    )
    (net (code "71") (name "Net-(Q7-G)") (class "Default")
      (node (ref "Q7") (pin "1") (pinfunction "G_1") (pintype "passive"))
      (node (ref "RL2") (pin "2") (pinfunction "2_2") (pintype "passive"))
    )
    (net (code "72") (name "Net-(R8-Pad2)") (class "Default")
      (node (ref "R8") (pin "2") (pinfunction "2_2") (pintype "passive"))
      (node (ref "U$3") (pin "TX1") (pinfunction "TX1_TX1") (pintype "bidirectional"))
    )
    (net (code "73") (name "Net-(R11-Pad2)") (class "Default")
      (node (ref "R11") (pin "2") (pinfunction "2_2") (pintype "passive"))
      (node (ref "U$3") (pin "RX1") (pinfunction "RX1_RX1") (pintype "bidirectional"))
    )
    (net (code "74") (name "Net-(R18-Pad2)") (class "Default")
      (node (ref "R18") (pin "2") (pinfunction "2_2") (pintype "passive"))
      (node (ref "U$1") (pin "SCK") (pinfunction "SCK_SCK") (pintype "bidirectional"))
    )
    (net (code "75") (name "Net-(R24-Pad2)") (class "Default")
      (node (ref "R24") (pin "2") (pinfunction "2_2") (pintype "passive"))
      (node (ref "X4") (pin "3") (pinfunction "3_3") (pintype "passive"))
    )
    (net (code "76") (name "Net-(R31-Pad2)") (class "Default")
      (node (ref "R31") (pin "2") (pinfunction "2_2") (pintype "passive"))
      (node (ref "X4") (pin "2") (pinfunction "2_2") (pintype "passive"))
    )
    (net (code "77") (name "Net-(U$1-CS)") (class "Default")
      (node (ref "R16") (pin "1") (pinfunction "1_1") (pintype "passive"))
      (node (ref "R17") (pin "1") (pinfunction "1_1") (pintype "passive"))
      (node (ref "U$1") (pin "CE") (pinfunction "CS_CE") (pintype "bidirectional"))
    )
    (net (code "78") (name "Net-(U$3-RNU)") (class "Default")
      (node (ref "LED9") (pin "C") (pinfunction "C_C") (pintype "passive"))
      (node (ref "U$3") (pin "RUN") (pinfunction "RNU_RUN") (pintype "bidirectional"))
    )
    (net (code "79") (name "Net-(U$4-UCAP)") (class "Default")
      (node (ref "C3") (pin "2") (pinfunction "2_2") (pintype "passive"))
      (node (ref "U$4") (pin "6") (pinfunction "UCAP_6") (pintype "bidirectional"))
    )
    (net (code "80") (name "Net-(X1B-S)") (class "Default")
      (node (ref "R20") (pin "2") (pinfunction "2_2") (pintype "passive"))
      (node (ref "X1") (pin "2") (pinfunction "S_2") (pintype "passive"))
    )
    (net (code "81") (name "Net-(X1C-S)") (class "Default")
      (node (ref "R19") (pin "2") (pinfunction "2_2") (pintype "passive"))
      (node (ref "X1") (pin "3") (pinfunction "S_3") (pintype "passive"))
    )
    (net (code "82") (name "Net-(X2B-S)") (class "Default")
      (node (ref "R10") (pin "2") (pinfunction "2_2") (pintype "passive"))
      (node (ref "RL6") (pin "2") (pinfunction "2_2") (pintype "passive"))
      (node (ref "X2") (pin "2") (pinfunction "S_2") (pintype "passive"))
    )
    (net (code "83") (name "Net-(X5B-S)") (class "Default")
      (node (ref "R21") (pin "2") (pinfunction "2_2") (pintype "passive"))
      (node (ref "RL8") (pin "2") (pinfunction "2_2") (pintype "passive"))
      (node (ref "X5") (pin "2") (pinfunction "S_2") (pintype "passive"))
    )
    (net (code "84") (name "VUSB") (class "Default")
      (node (ref "C7") (pin "2") (pinfunction "2_2") (pintype "passive"))
      (node (ref "D4") (pin "A") (pinfunction "A_A") (pintype "passive"))
      (node (ref "U$4") (pin "7") (pinfunction "VBUS_7") (pintype "bidirectional"))
      (node (ref "X4") (pin "1") (pinfunction "1_1") (pintype "passive"))
    )
    (net (code "85") (name "unconnected-(CFG-Pad2)") (class "Default")
      (node (ref "CFG") (pin "2") (pinfunction "2_2") (pintype "passive"))
    )
    (net (code "86") (name "unconnected-(CFG-Pad3)") (class "Default")
      (node (ref "CFG") (pin "3") (pinfunction "3_3") (pintype "passive"))
    )
    (net (code "87") (name "unconnected-(Q1-D-Pad4)") (class "Default")
      (node (ref "Q1") (pin "4") (pinfunction "D_4") (pintype "passive"))
    )
    (net (code "88") (name "unconnected-(Q2-D-Pad4)") (class "Default")
      (node (ref "Q2") (pin "4") (pinfunction "D_4") (pintype "passive"))
    )
    (net (code "89") (name "unconnected-(Q4-D-Pad4)") (class "Default")
      (node (ref "Q4") (pin "4") (pinfunction "D_4") (pintype "passive"))
    )
    (net (code "90") (name "unconnected-(Q5-D-Pad4)") (class "Default")
      (node (ref "Q5") (pin "4") (pinfunction "D_4") (pintype "passive"))
    )
    (net (code "91") (name "unconnected-(Q6-D-Pad4)") (class "Default")
      (node (ref "Q6") (pin "4") (pinfunction "D_4") (pintype "passive"))
    )
    (net (code "92") (name "unconnected-(RESET1-Pad1)") (class "Default")
      (node (ref "RESET1") (pin "1") (pinfunction "1_1") (pintype "passive"))
    )
    (net (code "93") (name "unconnected-(RESET1-Pad3)") (class "Default")
      (node (ref "RESET1") (pin "3") (pinfunction "3_3") (pintype "passive"))
    )
    (net (code "94") (name "unconnected-(U$3-PadRST)") (class "Default")
      (node (ref "U$3") (pin "RST") (pinfunction "RST_RST") (pintype "bidirectional"))
    )
    (net (code "95") (name "unconnected-(X4-Pad4)") (class "Default")
      (node (ref "X4") (pin "4") (pinfunction "4_4") (pintype "passive"))
    )
  )
)
